# hall4poles.net
KiCad netlist of a schematic drawn in Altium Designer
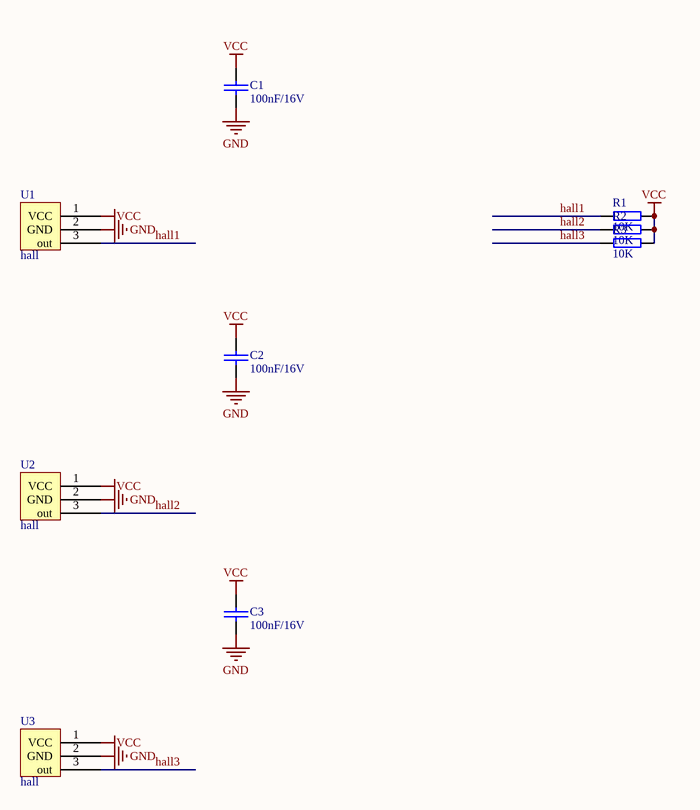
[diagram p0: hall4poles.SchDoc]

(export (version "E")
  (design (tool "Eeschema 10.0.6"))
  (components
    (comp (ref "C1")
      (value "100nF/16V")
      (footprint "C0603")
      (description "Capacitor")
      (libsource (lib "*") (part "CAP"))
    )
    (comp (ref "C2")
      (value "100nF/16V")
      (footprint "C0603")
      (description "Capacitor")
      (libsource (lib "*") (part "CAP"))
    )
    (comp (ref "C3")
      (value "100nF/16V")
      (footprint "C0603")
      (description "Capacitor")
      (libsource (lib "*") (part "CAP"))
    )
    (comp (ref "R1") (value "10K") (footprint "R0603") (libsource (lib "zijianku") (part "Resistance")))
    (comp (ref "R2") (value "10K") (footprint "R0603") (libsource (lib "zijianku") (part "Resistance")))
    (comp (ref "R3") (value "10K") (footprint "R0603") (libsource (lib "zijianku") (part "Resistance")))
    (comp (ref "U1") (value "hall") (footprint "TO-92S") (libsource (lib "zijianku") (part "hall")))
    (comp (ref "U2") (value "hall") (footprint "TO-92S") (libsource (lib "zijianku") (part "hall")))
    (comp (ref "U3") (value "hall") (footprint "TO-92S") (libsource (lib "zijianku") (part "hall")))
  )
  (nets
    (net (code "1") (name "/hall1") (class "Default")
      (node (ref "R1") (pin "1") (pintype "passive"))
      (node (ref "U1") (pin "3") (pinfunction "out_3") (pintype "passive"))
    )
    (net (code "2") (name "/hall2") (class "Default")
      (node (ref "R2") (pin "1") (pintype "passive"))
      (node (ref "U2") (pin "3") (pinfunction "out_3") (pintype "passive"))
    )
    (net (code "3") (name "/hall3") (class "Default")
      (node (ref "R3") (pin "1") (pintype "passive"))
      (node (ref "U3") (pin "3") (pinfunction "out_3") (pintype "passive"))
    )
    (net (code "4") (name "GND") (class "Default")
      (node (ref "C1") (pin "1") (pinfunction "1_1") (pintype "passive"))
      (node (ref "C2") (pin "1") (pinfunction "1_1") (pintype "passive"))
      (node (ref "C3") (pin "1") (pinfunction "1_1") (pintype "passive"))
      (node (ref "U1") (pin "2") (pinfunction "GND_2") (pintype "passive"))
      (node (ref "U2") (pin "2") (pinfunction "GND_2") (pintype "passive"))
      (node (ref "U3") (pin "2") (pinfunction "GND_2") (pintype "passive"))
    )
    (net (code "5") (name "VCC") (class "Default")
      (node (ref "C1") (pin "2") (pinfunction "2_2") (pintype "passive"))
      (node (ref "C2") (pin "2") (pinfunction "2_2") (pintype "passive"))
      (node (ref "C3") (pin "2") (pinfunction "2_2") (pintype "passive"))
      (node (ref "R1") (pin "2") (pintype "passive"))
      (node (ref "R2") (pin "2") (pintype "passive"))
      (node (ref "R3") (pin "2") (pintype "passive"))
      (node (ref "U1") (pin "1") (pinfunction "VCC_1") (pintype "passive"))
      (node (ref "U2") (pin "1") (pinfunction "VCC_1") (pintype "passive"))
      (node (ref "U3") (pin "1") (pinfunction "VCC_1") (pintype "passive"))
    )
  )
)
